# Power.net
KiCad netlist of a schematic drawn in Altium Designer
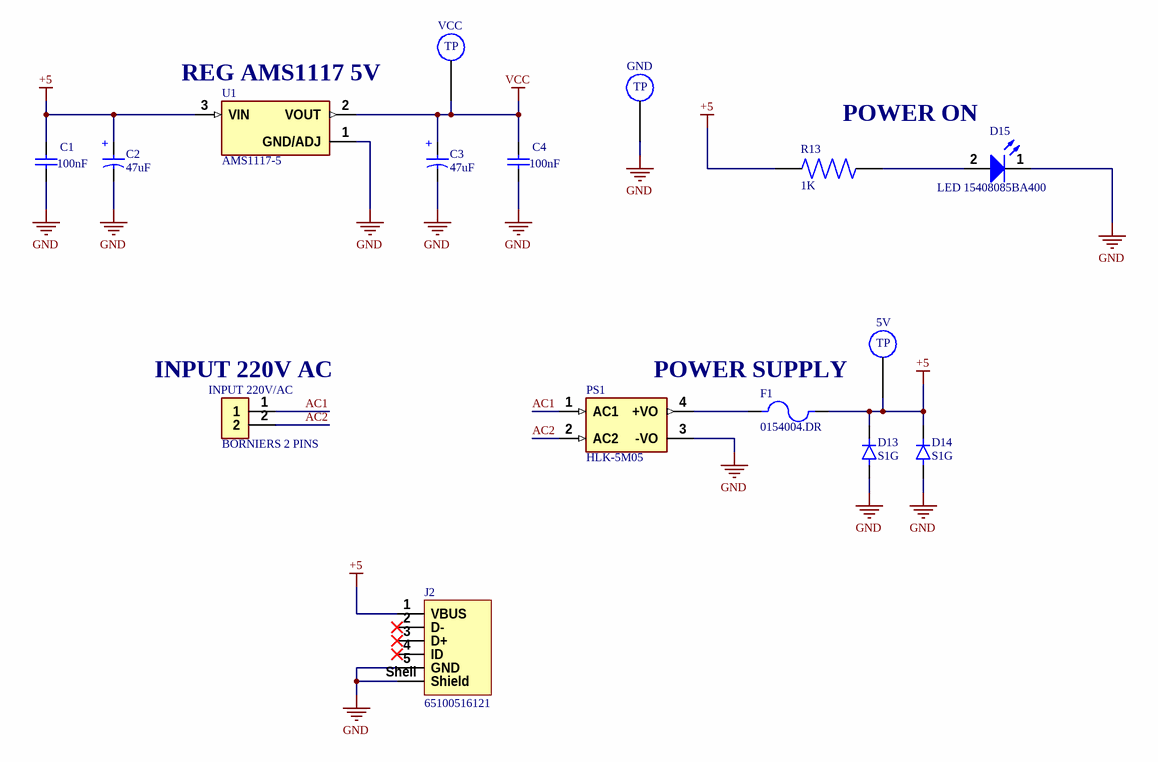
[diagram p0: Power.SchDoc]

(export (version "E")
  (design (tool "Eeschema 10.0.6"))
  (components
    (comp (ref "5V")
      (value "TEST POINT")
      (footprint "TEST POINT")
      (libsource (lib "Ala Hassine v1.0") (part "TEST POINT"))
    )
    (comp (ref "C1")
      (value "100nF")
      (footprint "WCAP-CSGP_0603_L1.6W0.8H0.8_Reflow")
      (description "WCAP-CSGP Multilayer Ceramic Chip Capacitor, General Purpose, size 0603, 100nF, 25V")
      (fields
        (field (name "MANUFACTURER PART NUMBER") "885012206071")
        (field (name "MANUFACTURER") "Wurth Elektronik")
      )
      (libsource (lib "Ala Hassine v1.0") (part "885012206071"))
    )
    (comp (ref "C2")
      (value "Cap 865080443007")
      (footprint "Cap 865080443007")
      (description "WCAP-ASLI Aluminum Electrolytic Capacitor, V-Chip, D6.3 x H5.5mm, 47uF, 25V")
      (fields
        (field (name "MANUFACTURER PART NUMBER") "865080443007")
        (field (name "MANUFACTURER") "Wurth Elektronik")
        (field (name "CAPACITANCE") "47uF")
      )
      (libsource (lib "Ala Hassine v1.0") (part "Cap 865080443007"))
    )
    (comp (ref "C3")
      (value "Cap 865080443007")
      (footprint "Cap 865080443007")
      (description "WCAP-ASLI Aluminum Electrolytic Capacitor, V-Chip, D6.3 x H5.5mm, 47uF, 25V")
      (fields
        (field (name "MANUFACTURER PART NUMBER") "865080443007")
        (field (name "MANUFACTURER") "Wurth Elektronik")
        (field (name "CAPACITANCE") "47uF")
      )
      (libsource (lib "Ala Hassine v1.0") (part "Cap 865080443007"))
    )
    (comp (ref "C4")
      (value "100nF")
      (footprint "WCAP-CSGP_0603_L1.6W0.8H0.8_Reflow")
      (description "WCAP-CSGP Multilayer Ceramic Chip Capacitor, General Purpose, size 0603, 100nF, 25V")
      (fields
        (field (name "MANUFACTURER PART NUMBER") "885012206071")
        (field (name "MANUFACTURER") "Wurth Elektronik")
      )
      (libsource (lib "Ala Hassine v1.0") (part "885012206071"))
    )
    (comp (ref "D13")
      (value "S1G")
      (footprint "S1G")
      (description "Diode Standard 400 V 1A Surface Mount DO-214AC (SMA)")
      (fields (field (name "MF") "ON Semiconductor"))
      (libsource (lib "Ala Hassine v1.0") (part "S1G"))
    )
    (comp (ref "D14")
      (value "S1G")
      (footprint "S1G")
      (description "Diode Standard 400 V 1A Surface Mount DO-214AC (SMA)")
      (fields (field (name "MF") "ON Semiconductor"))
      (libsource (lib "Ala Hassine v1.0") (part "S1G"))
    )
    (comp (ref "D15")
      (value "LED 15408085BA400")
      (footprint "LED 15408085BA400")
      (description "SMT Infrared Chip LED Infrared Waterclear, body 2x1.3mm, size 0805, Infrared, 1.4V, 140°")
      (fields
        (field (name "MANUFACTURER PART NUMBER") "15408085BA400")
        (field (name "MANUFACTURER") "Wurth Elektronik")
      )
      (libsource (lib "Ala Hassine v1.0") (part "LED 15408085BA400"))
    )
    (comp (ref "F1")
      (value "0154004.DR")
      (footprint "0154004.DR")
      (description "Nano2 SMD FF submin fuse w/holder, 4A ¦ Littelfuse 0154004.DR")
      (fields (field (name "MF") "Littelfuse Inc."))
      (libsource (lib "Ala Hassine v1.0") (part "0154004.DR"))
    )
    (comp (ref "GND")
      (value "TEST POINT")
      (footprint "TEST POINT")
      (libsource (lib "Ala Hassine v1.0") (part "TEST POINT"))
    )
    (comp (ref "INPUT 220V/AC")
      (value "BORNIERS 2 PINS")
      (footprint "BORNIERS 2 PINS")
      (description "Terminal Block Connector Wire Receptacle 2")
      (libsource (lib "Ala Hassine v1.0") (part "BORNIERS 2 PINS"))
    )
    (comp (ref "J2")
      (value "65100516121")
      (footprint "WR-USB-65100516121")
      (description "WR-COM Mini USB 2.0 Type B SMT Horizontal 5 Contacts")
      (fields (field (name "MANUFACTURER") "Wurth Elektronik"))
      (libsource (lib "Ala Hassine v1.0") (part "WR-USB-65100516121"))
    )
    (comp (ref "PS1")
      (value "HLK-5M05")
      (footprint "Ala Hassine v1.0:HLK-5M05")
      (description "AC-DC Power Supply Module HLK-5M05 220V to 5V 1A")
      (fields (field (name "MF") "{'manufacturer': u'Hi-link'}"))
      (libsource (lib "Ala Hassine v1.0") (part "HLK-5M05"))
    )
    (comp (ref "R13")
      (value "1K")
      (footprint "RES FCR1206J10R")
      (description "RES 1206 10 Ohm 5% 1/8W ±500ppm/°C Molded SMD SMD T/R")
      (fields (field (name "TOLERANCE") "5%") (field (name "MP") "FCR1206J10R"))
      (libsource (lib "Ala Hassine v1.0") (part "RES FCR1206J10R"))
    )
    (comp (ref "U1")
      (value "AMS1117-5")
      (footprint "AMS1117-5")
      (description "Sot223/Pkg 1-Amp 5-Volt Low Drop Out Voltage Regulatator")
      (fields (field (name "MF") "Advanced Monolithic Systems") (field (name "MP") "AMS1117-3.3"))
      (libsource (lib "Ala Hassine v1.0") (part "AMS1117-5"))
    )
    (comp (ref "VCC")
      (value "TEST POINT")
      (footprint "TEST POINT")
      (libsource (lib "Ala Hassine v1.0") (part "TEST POINT"))
    )
  )
  (nets
    (net (code "1") (name "+5") (class "Default")
      (node (ref "5V") (pin "1") (pinfunction "1_1") (pintype "passive"))
      (node (ref "C1") (pin "2") (pinfunction "2_2") (pintype "passive"))
      (node (ref "C2") (pin "1") (pinfunction "P_1") (pintype "passive"))
      (node (ref "D13") (pin "1") (pinfunction "K_1") (pintype "passive"))
      (node (ref "D14") (pin "1") (pinfunction "K_1") (pintype "passive"))
      (node (ref "F1") (pin "2") (pinfunction "2_2") (pintype "passive"))
      (node (ref "J2") (pin "1") (pinfunction "VBUS_1") (pintype "passive"))
      (node (ref "R13") (pin "1") (pinfunction "1_1") (pintype "passive"))
      (node (ref "U1") (pin "3") (pinfunction "VIN_3") (pintype "input"))
    )
    (net (code "2") (name "/AC1") (class "Default")
      (node (ref "INPUT 220V/AC") (pin "1") (pinfunction "1_1") (pintype "passive"))
      (node (ref "PS1") (pin "1") (pinfunction "AC1_1") (pintype "input"))
    )
    (net (code "3") (name "/AC2") (class "Default")
      (node (ref "INPUT 220V/AC") (pin "2") (pinfunction "2_2") (pintype "passive"))
      (node (ref "PS1") (pin "2") (pinfunction "AC2_2") (pintype "input"))
    )
    (net (code "4") (name "GND") (class "Default")
      (node (ref "C1") (pin "1") (pinfunction "1_1") (pintype "passive"))
      (node (ref "C2") (pin "2") (pinfunction "N_2") (pintype "passive"))
      (node (ref "C3") (pin "2") (pinfunction "N_2") (pintype "passive"))
      (node (ref "C4") (pin "1") (pinfunction "1_1") (pintype "passive"))
      (node (ref "D13") (pin "2") (pinfunction "A_2") (pintype "passive"))
      (node (ref "D14") (pin "2") (pinfunction "A_2") (pintype "passive"))
      (node (ref "D15") (pin "1") (pinfunction "K_1") (pintype "passive"))
      (node (ref "GND") (pin "1") (pinfunction "1_1") (pintype "passive"))
      (node (ref "J2") (pin "5") (pinfunction "GND_5") (pintype "passive"))
      (node (ref "J2") (pin "Shell") (pinfunction "Shield_Shell") (pintype "passive"))
      (node (ref "PS1") (pin "3") (pinfunction "-VO_3") (pintype "power_in"))
      (node (ref "U1") (pin "1") (pinfunction "GND/ADJ_1") (pintype "power_in"))
    )
    (net (code "5") (name "Net-(D15-A)") (class "Default")
      (node (ref "D15") (pin "2") (pinfunction "A_2") (pintype "passive"))
      (node (ref "R13") (pin "2") (pinfunction "2_2") (pintype "passive"))
    )
    (net (code "6") (name "Net-(PS1-+VO)") (class "Default")
      (node (ref "F1") (pin "1") (pinfunction "1_1") (pintype "passive"))
      (node (ref "PS1") (pin "4") (pinfunction "+VO_4") (pintype "output"))
    )
    (net (code "7") (name "VCC") (class "Default")
      (node (ref "C3") (pin "1") (pinfunction "P_1") (pintype "passive"))
      (node (ref "C4") (pin "2") (pinfunction "2_2") (pintype "passive"))
      (node (ref "U1") (pin "2") (pinfunction "VOUT_2") (pintype "output"))
      (node (ref "VCC") (pin "1") (pinfunction "1_1") (pintype "passive"))
    )
    (net (code "8") (name "unconnected-(J2-D+-Pad3)") (class "Default")
      (node (ref "J2") (pin "3") (pinfunction "D+_3") (pintype "passive+no_connect"))
    )
    (net (code "9") (name "unconnected-(J2-D--Pad2)") (class "Default")
      (node (ref "J2") (pin "2") (pinfunction "D-_2") (pintype "passive+no_connect"))
    )
    (net (code "10") (name "unconnected-(J2-ID-Pad4)") (class "Default")
      (node (ref "J2") (pin "4") (pinfunction "ID_4") (pintype "passive+no_connect"))
    )
  )
)
